# piezo-preamp-alex-rice-FETS_v3.net
KiCad netlist of a schematic drawn in EAGLE
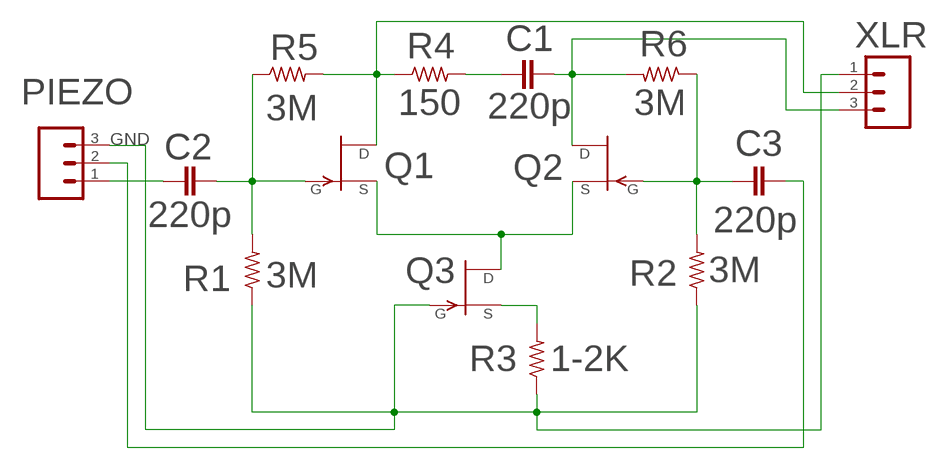
[diagram p0: schematic, sheet 1]

(export (version "E")
  (design (tool "Eeschema 10.0.6"))
  (components
    (comp (ref "C1")
      (value "220p")
      (footprint "eagle-import:C050-030X075")
      (libsource (lib "eagle-import") (part "C-EU050-030X075"))
    )
    (comp (ref "C2")
      (value "220p")
      (footprint "eagle-import:C050-030X075")
      (libsource (lib "eagle-import") (part "C-EU050-030X075"))
    )
    (comp (ref "C3")
      (value "220p")
      (footprint "eagle-import:C050-030X075")
      (libsource (lib "eagle-import") (part "C-EU050-030X075"))
    )
    (comp (ref "PIEZO")
      (value "M03LOCK")
      (footprint "eagle-import:1X03_LOCK")
      (libsource (lib "eagle-import") (part "M03LOCK"))
    )
    (comp (ref "Q1")
      (value "2N3819")
      (footprint "eagle-import:TO92")
      (libsource (lib "eagle-import") (part "2N3819-WIDETO92_WIDE"))
    )
    (comp (ref "Q2")
      (value "2N3819-WIDETO92_WIDE")
      (footprint "eagle-import:TO92")
      (libsource (lib "eagle-import") (part "2N3819-WIDETO92_WIDE"))
    )
    (comp (ref "Q3")
      (value "2N3819-WIDETO92_WIDE")
      (footprint "eagle-import:TO92")
      (libsource (lib "eagle-import") (part "2N3819-WIDETO92_WIDE"))
    )
    (comp (ref "R1")
      (value "3M")
      (footprint "eagle-import:0204_5")
      (libsource (lib "eagle-import") (part "R-US_0204/5"))
    )
    (comp (ref "R2")
      (value "3M")
      (footprint "eagle-import:0204_5")
      (libsource (lib "eagle-import") (part "R-US_0204/5"))
    )
    (comp (ref "R3")
      (value "1-2K")
      (footprint "eagle-import:0204_5")
      (libsource (lib "eagle-import") (part "R-US_0204/5"))
    )
    (comp (ref "R4")
      (value "150")
      (footprint "eagle-import:0204_5")
      (libsource (lib "eagle-import") (part "resistor_R-US_0204/5"))
    )
    (comp (ref "R5")
      (value "3M")
      (footprint "eagle-import:0204_5")
      (libsource (lib "eagle-import") (part "R-US_0204/5"))
    )
    (comp (ref "R6")
      (value "3M")
      (footprint "eagle-import:0204_5")
      (libsource (lib "eagle-import") (part "R-US_0204/5"))
    )
    (comp (ref "XLR")
      (value "M03LOCK")
      (footprint "eagle-import:1X03_LOCK")
      (libsource (lib "eagle-import") (part "M03LOCK"))
    )
  )
  (nets
    (net (code "1") (name "Net-(C1-Pad1)") (class "Default")
      (node (ref "C1") (pin "1") (pinfunction "1_1") (pintype "passive"))
      (node (ref "R4") (pin "2") (pinfunction "2_2") (pintype "passive"))
    )
    (net (code "2") (name "Net-(C2-Pad1)") (class "Default")
      (node (ref "C2") (pin "1") (pinfunction "1_1") (pintype "passive"))
      (node (ref "PIEZO") (pin "1") (pinfunction "1_1") (pintype "passive"))
    )
    (net (code "3") (name "Net-(C3-Pad2)") (class "Default")
      (node (ref "C3") (pin "2") (pinfunction "2_2") (pintype "passive"))
      (node (ref "PIEZO") (pin "2") (pinfunction "2_2") (pintype "passive"))
    )
    (net (code "4") (name "Net-(Q1-D)") (class "Default")
      (node (ref "Q1") (pin "1") (pinfunction "D_1") (pintype "passive"))
      (node (ref "R4") (pin "1") (pinfunction "1_1") (pintype "passive"))
      (node (ref "R5") (pin "2") (pinfunction "2_2") (pintype "passive"))
      (node (ref "XLR") (pin "2") (pinfunction "2_2") (pintype "passive"))
    )
    (net (code "5") (name "Net-(Q1-G)") (class "Default")
      (node (ref "C2") (pin "2") (pinfunction "2_2") (pintype "passive"))
      (node (ref "Q1") (pin "2") (pinfunction "G_2") (pintype "passive"))
      (node (ref "R1") (pin "2") (pinfunction "2_2") (pintype "passive"))
      (node (ref "R5") (pin "1") (pinfunction "1_1") (pintype "passive"))
    )
    (net (code "6") (name "Net-(Q1-S)") (class "Default")
      (node (ref "Q1") (pin "3") (pinfunction "S_3") (pintype "passive"))
      (node (ref "Q2") (pin "3") (pinfunction "S_3") (pintype "passive"))
      (node (ref "Q3") (pin "1") (pinfunction "D_1") (pintype "passive"))
    )
    (net (code "7") (name "Net-(Q2-D)") (class "Default")
      (node (ref "C1") (pin "2") (pinfunction "2_2") (pintype "passive"))
      (node (ref "Q2") (pin "1") (pinfunction "D_1") (pintype "passive"))
      (node (ref "R6") (pin "2") (pinfunction "2_2") (pintype "passive"))
      (node (ref "XLR") (pin "3") (pinfunction "3_3") (pintype "passive"))
    )
    (net (code "8") (name "Net-(Q2-G)") (class "Default")
      (node (ref "C3") (pin "1") (pinfunction "1_1") (pintype "passive"))
      (node (ref "Q2") (pin "2") (pinfunction "G_2") (pintype "passive"))
      (node (ref "R2") (pin "2") (pinfunction "2_2") (pintype "passive"))
      (node (ref "R6") (pin "1") (pinfunction "1_1") (pintype "passive"))
    )
    (net (code "9") (name "Net-(Q3-G)") (class "Default")
      (node (ref "PIEZO") (pin "3") (pinfunction "3_3") (pintype "passive"))
      (node (ref "Q3") (pin "2") (pinfunction "G_2") (pintype "passive"))
      (node (ref "R1") (pin "1") (pinfunction "1_1") (pintype "passive"))
      (node (ref "R2") (pin "1") (pinfunction "1_1") (pintype "passive"))
      (node (ref "R3") (pin "1") (pinfunction "1_1") (pintype "passive"))
      (node (ref "XLR") (pin "1") (pinfunction "1_1") (pintype "passive"))
    )
    (net (code "10") (name "Net-(Q3-S)") (class "Default")
      (node (ref "Q3") (pin "3") (pinfunction "S_3") (pintype "passive"))
      (node (ref "R3") (pin "2") (pinfunction "2_2") (pintype "passive"))
    )
  )
)
